# Power.net
KiCad netlist of a schematic drawn in Altium Designer
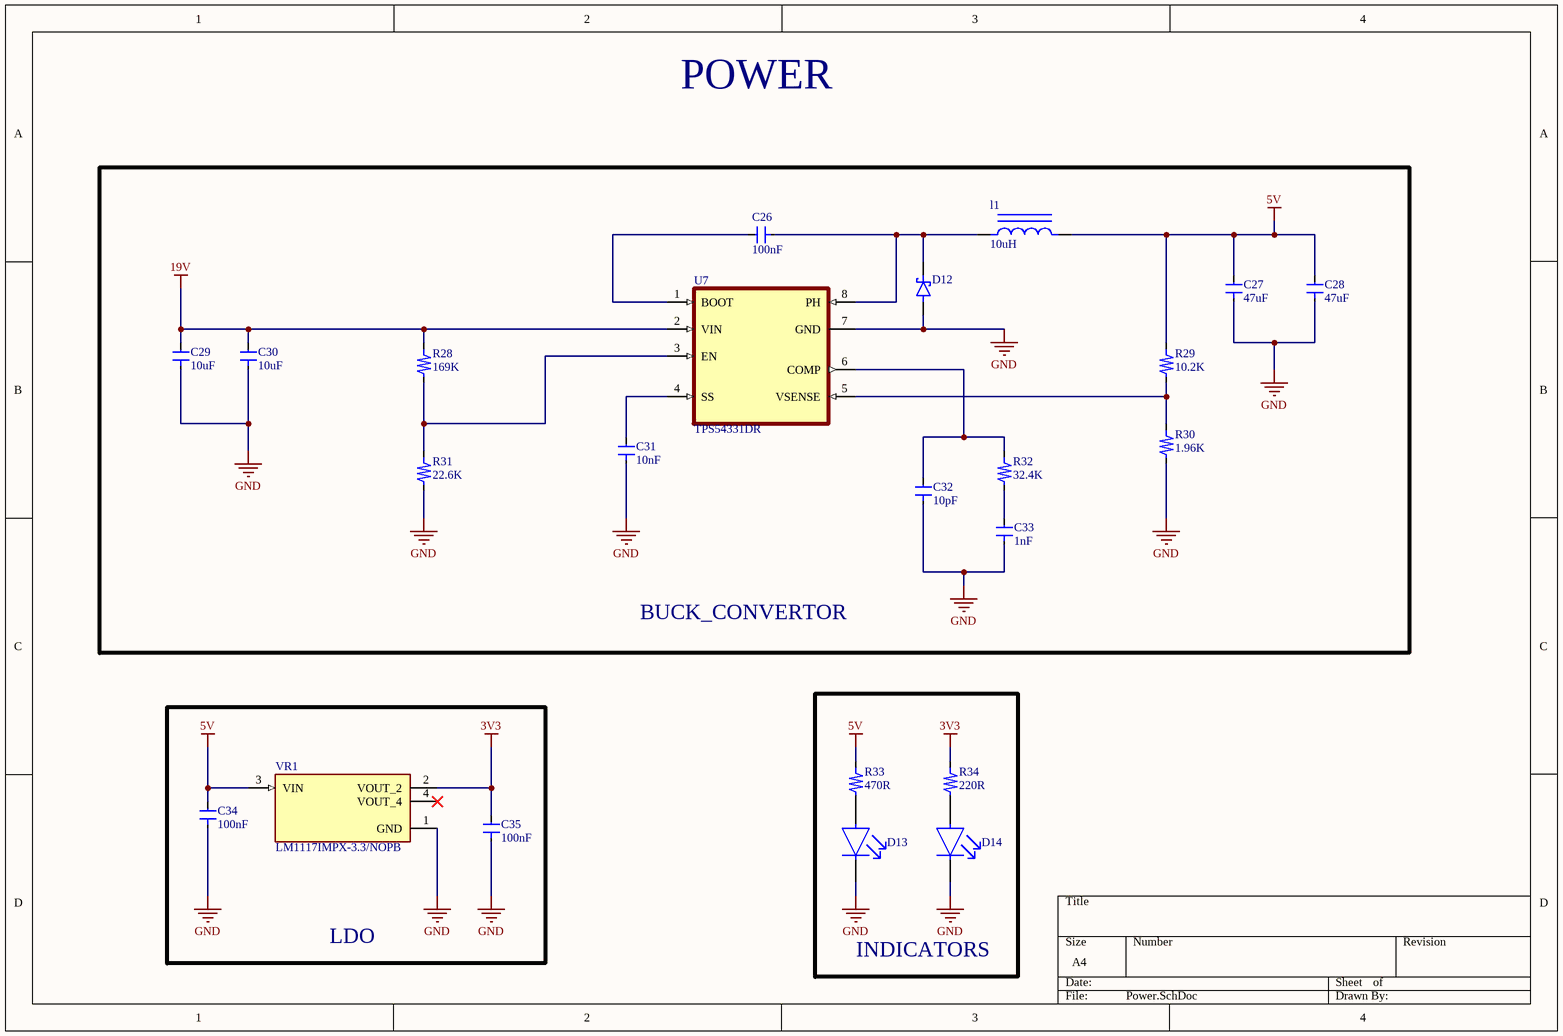
[diagram p0: Power.SchDoc]

(export (version "E")
  (design (tool "Eeschema 10.0.6"))
  (components
    (comp (ref "C26")
      (value "100nF")
      (footprint "CAP 0603")
      (fields (field (name "PART NUMBER") "CC0603JRX7R9BB104"))
      (libsource (lib "Schlib2") (part "Capasitor"))
    )
    (comp (ref "C27")
      (value "47uF")
      (footprint "CAP 0603")
      (fields (field (name "PART NUMBER") "GRM188R60J476ME15D"))
      (libsource (lib "Schlib2") (part "Capasitor"))
    )
    (comp (ref "C28")
      (value "47uF")
      (footprint "CAP 0603")
      (fields (field (name "PART NUMBER") "GRM188R60J476ME15D"))
      (libsource (lib "Schlib2") (part "Capasitor"))
    )
    (comp (ref "C29")
      (value "10uF")
      (footprint "CAP 0805")
      (fields (field (name "PART NUMBER") "GRM21BR61H106KE43L"))
      (libsource (lib "Schlib2") (part "Capasitor"))
    )
    (comp (ref "C30")
      (value "10uF")
      (footprint "CAP 0805")
      (fields (field (name "PART NUMBER") "GRM21BR61H106KE43L"))
      (libsource (lib "Schlib2") (part "Capasitor"))
    )
    (comp (ref "C31")
      (value "10nF")
      (footprint "CAP 0603")
      (fields (field (name "PART NUMBER") "CC0603JRX7R9BB103"))
      (libsource (lib "Schlib2") (part "Capasitor"))
    )
    (comp (ref "C32")
      (value "10pF")
      (footprint "CAP 0603")
      (fields (field (name "PART NUMBER") "GRM1885C1H100FA01D"))
      (libsource (lib "Schlib2") (part "Capasitor"))
    )
    (comp (ref "C33")
      (value "1nF")
      (footprint "CAP 0603")
      (fields (field (name "PART NUMBER") "GRM1885C1H102FA01D"))
      (libsource (lib "Schlib2") (part "Capasitor"))
    )
    (comp (ref "C34")
      (value "100nF")
      (footprint "CAP 0603")
      (fields (field (name "PART NUMBER") "CC0603JRX7R9BB104"))
      (libsource (lib "Schlib2") (part "Capasitor"))
    )
    (comp (ref "C35")
      (value "100nF")
      (footprint "CAP 0603")
      (fields (field (name "PART NUMBER") "CC0603JRX7R9BB104"))
      (libsource (lib "Schlib2") (part "Capasitor"))
    )
    (comp (ref "D12")
      (value "B340A-E3/61T")
      (footprint "DIOM5126X229N")
      (description "Diode Schottky 40 V 3A Surface Mount DO-214AC (SMA)")
      (libsource (lib "Schlib2") (part "B340A-E3/61T"))
    )
    (comp (ref "D13")
      (value "LED")
      (footprint "LED")
      (fields (field (name "PART NUMBER") "XL-2012SURC"))
      (libsource (lib "Schlib2") (part "LED"))
    )
    (comp (ref "D14")
      (value "LED")
      (footprint "LED")
      (fields (field (name "PART NUMBER") "XL-2012SURC"))
      (libsource (lib "Schlib2") (part "LED"))
    )
    (comp (ref "l1")
      (value "10uH")
      (footprint "INDUCTOR")
      (fields (field (name "PART NUMBER") "YPRH8D43-100M"))
      (libsource (lib "Schlib2") (part "Iductor"))
    )
    (comp (ref "R28")
      (value "169K")
      (footprint "RES 0603")
      (fields (field (name "PART NUMBER") "AR03FTC1693"))
      (libsource (lib "Schlib2") (part "Resistor"))
    )
    (comp (ref "R29")
      (value "10.2K")
      (footprint "RES 0603")
      (fields (field (name "PART NUMBER") "RS-03K1022FT"))
      (libsource (lib "Schlib2") (part "Resistor"))
    )
    (comp (ref "R30")
      (value "1.96K")
      (footprint "RES 0603")
      (fields (field (name "PART NUMBER") "FRC0603F1961TS"))
      (libsource (lib "Schlib2") (part "Resistor"))
    )
    (comp (ref "R31")
      (value "22.6K")
      (footprint "RES 0603")
      (fields (field (name "PART NUMBER") "RS-03K2262FT"))
      (libsource (lib "Schlib2") (part "Resistor"))
    )
    (comp (ref "R32")
      (value "32.4K")
      (footprint "RES 0603")
      (fields (field (name "PART NUMBER") "RS-03K3242FT"))
      (libsource (lib "Schlib2") (part "Resistor"))
    )
    (comp (ref "R33")
      (value "470R")
      (footprint "RES 0603")
      (fields (field (name "PART NUMBER") "CRCW0603470RJNEA"))
      (libsource (lib "Schlib2") (part "Resistor"))
    )
    (comp (ref "R34")
      (value "220R")
      (footprint "RES 0603")
      (fields (field (name "PART NUMBER") "RC0603JR-07220RL"))
      (libsource (lib "Schlib2") (part "Resistor"))
    )
    (comp (ref "U7")
      (value "TPS54331DR")
      (footprint "SOIC127P599X175-8N")
      (description "3.5V to 28V Input, 3A, 570kHz Step-Down Converter with Eco-mode")
      (libsource (lib "Schlib2") (part "TPS54331DR"))
    )
    (comp (ref "VR1")
      (value "LM1117IMPX-3.3/NOPB")
      (footprint "VREG_LM1117IMPX-3.3/NOPB")
      (description "800-mA 15-V linear voltage regulator")
      (libsource (lib "Schlib2") (part "LM1117IMPX-3.3/NOPB"))
    )
  )
  (nets
    (net (code "1") (name "3V3") (class "Default")
      (node (ref "C35") (pin "2") (pinfunction "2_2") (pintype "passive"))
      (node (ref "R34") (pin "1") (pinfunction "1_1") (pintype "passive"))
      (node (ref "VR1") (pin "2") (pinfunction "VOUT_2_2") (pintype "passive"))
    )
    (net (code "2") (name "5V") (class "Default")
      (node (ref "C27") (pin "2") (pinfunction "2_2") (pintype "passive"))
      (node (ref "C28") (pin "2") (pinfunction "2_2") (pintype "passive"))
      (node (ref "C34") (pin "2") (pinfunction "2_2") (pintype "passive"))
      (node (ref "R29") (pin "1") (pinfunction "1_1") (pintype "passive"))
      (node (ref "R33") (pin "1") (pinfunction "1_1") (pintype "passive"))
      (node (ref "VR1") (pin "3") (pinfunction "VIN_3") (pintype "input"))
      (node (ref "l1") (pin "2") (pinfunction "2_2") (pintype "passive"))
    )
    (net (code "3") (name "19V") (class "Default")
      (node (ref "C29") (pin "2") (pinfunction "2_2") (pintype "passive"))
      (node (ref "C30") (pin "2") (pinfunction "2_2") (pintype "passive"))
      (node (ref "R28") (pin "1") (pinfunction "1_1") (pintype "passive"))
      (node (ref "U7") (pin "2") (pinfunction "VIN_2") (pintype "input"))
    )
    (net (code "4") (name "GND") (class "Default")
      (node (ref "C27") (pin "1") (pinfunction "1_1") (pintype "passive"))
      (node (ref "C28") (pin "1") (pinfunction "1_1") (pintype "passive"))
      (node (ref "C29") (pin "1") (pinfunction "1_1") (pintype "passive"))
      (node (ref "C30") (pin "1") (pinfunction "1_1") (pintype "passive"))
      (node (ref "C31") (pin "1") (pinfunction "1_1") (pintype "passive"))
      (node (ref "C32") (pin "1") (pinfunction "1_1") (pintype "passive"))
      (node (ref "C33") (pin "1") (pinfunction "1_1") (pintype "passive"))
      (node (ref "C34") (pin "1") (pinfunction "1_1") (pintype "passive"))
      (node (ref "C35") (pin "1") (pinfunction "1_1") (pintype "passive"))
      (node (ref "D12") (pin "A") (pinfunction "A_A") (pintype "passive"))
      (node (ref "D13") (pin "1") (pinfunction "C_1") (pintype "passive"))
      (node (ref "D14") (pin "1") (pinfunction "C_1") (pintype "passive"))
      (node (ref "R30") (pin "2") (pinfunction "2_2") (pintype "passive"))
      (node (ref "R31") (pin "2") (pinfunction "2_2") (pintype "passive"))
      (node (ref "U7") (pin "7") (pinfunction "GND_7") (pintype "power_in"))
      (node (ref "VR1") (pin "1") (pinfunction "GND_1") (pintype "passive"))
    )
    (net (code "5") (name "Net-(C33-Pad2)") (class "Default")
      (node (ref "C33") (pin "2") (pinfunction "2_2") (pintype "passive"))
      (node (ref "R32") (pin "2") (pinfunction "2_2") (pintype "passive"))
    )
    (net (code "6") (name "Net-(D13-A)") (class "Default")
      (node (ref "D13") (pin "2") (pinfunction "A_2") (pintype "passive"))
      (node (ref "R33") (pin "2") (pinfunction "2_2") (pintype "passive"))
    )
    (net (code "7") (name "Net-(D14-A)") (class "Default")
      (node (ref "D14") (pin "2") (pinfunction "A_2") (pintype "passive"))
      (node (ref "R34") (pin "2") (pinfunction "2_2") (pintype "passive"))
    )
    (net (code "8") (name "Net-(U7-BOOT)") (class "Default")
      (node (ref "C26") (pin "2") (pinfunction "2_2") (pintype "passive"))
      (node (ref "U7") (pin "1") (pinfunction "BOOT_1") (pintype "input"))
    )
    (net (code "9") (name "Net-(U7-COMP)") (class "Default")
      (node (ref "C32") (pin "2") (pinfunction "2_2") (pintype "passive"))
      (node (ref "R32") (pin "1") (pinfunction "1_1") (pintype "passive"))
      (node (ref "U7") (pin "6") (pinfunction "COMP_6") (pintype "output"))
    )
    (net (code "10") (name "Net-(U7-EN)") (class "Default")
      (node (ref "R28") (pin "2") (pinfunction "2_2") (pintype "passive"))
      (node (ref "R31") (pin "1") (pinfunction "1_1") (pintype "passive"))
      (node (ref "U7") (pin "3") (pinfunction "EN_3") (pintype "input"))
    )
    (net (code "11") (name "Net-(U7-PH)") (class "Default")
      (node (ref "C26") (pin "1") (pinfunction "1_1") (pintype "passive"))
      (node (ref "D12") (pin "C") (pinfunction "C_C") (pintype "passive"))
      (node (ref "U7") (pin "8") (pinfunction "PH_8") (pintype "input"))
      (node (ref "l1") (pin "1") (pinfunction "1_1") (pintype "passive"))
    )
    (net (code "12") (name "Net-(U7-SS)") (class "Default")
      (node (ref "C31") (pin "2") (pinfunction "2_2") (pintype "passive"))
      (node (ref "U7") (pin "4") (pinfunction "SS_4") (pintype "input"))
    )
    (net (code "13") (name "Net-(U7-VSENSE)") (class "Default")
      (node (ref "R29") (pin "2") (pinfunction "2_2") (pintype "passive"))
      (node (ref "R30") (pin "1") (pinfunction "1_1") (pintype "passive"))
      (node (ref "U7") (pin "5") (pinfunction "VSENSE_5") (pintype "input"))
    )
    (net (code "14") (name "unconnected-(VR1-VOUT_4-Pad4)") (class "Default")
      (node (ref "VR1") (pin "4") (pinfunction "VOUT_4_4") (pintype "passive+no_connect"))
    )
  )
)
